# MINI_SAM_TQFP_2_54_BB_2017_01_17_004.net
KiCad netlist of a schematic drawn in EAGLE
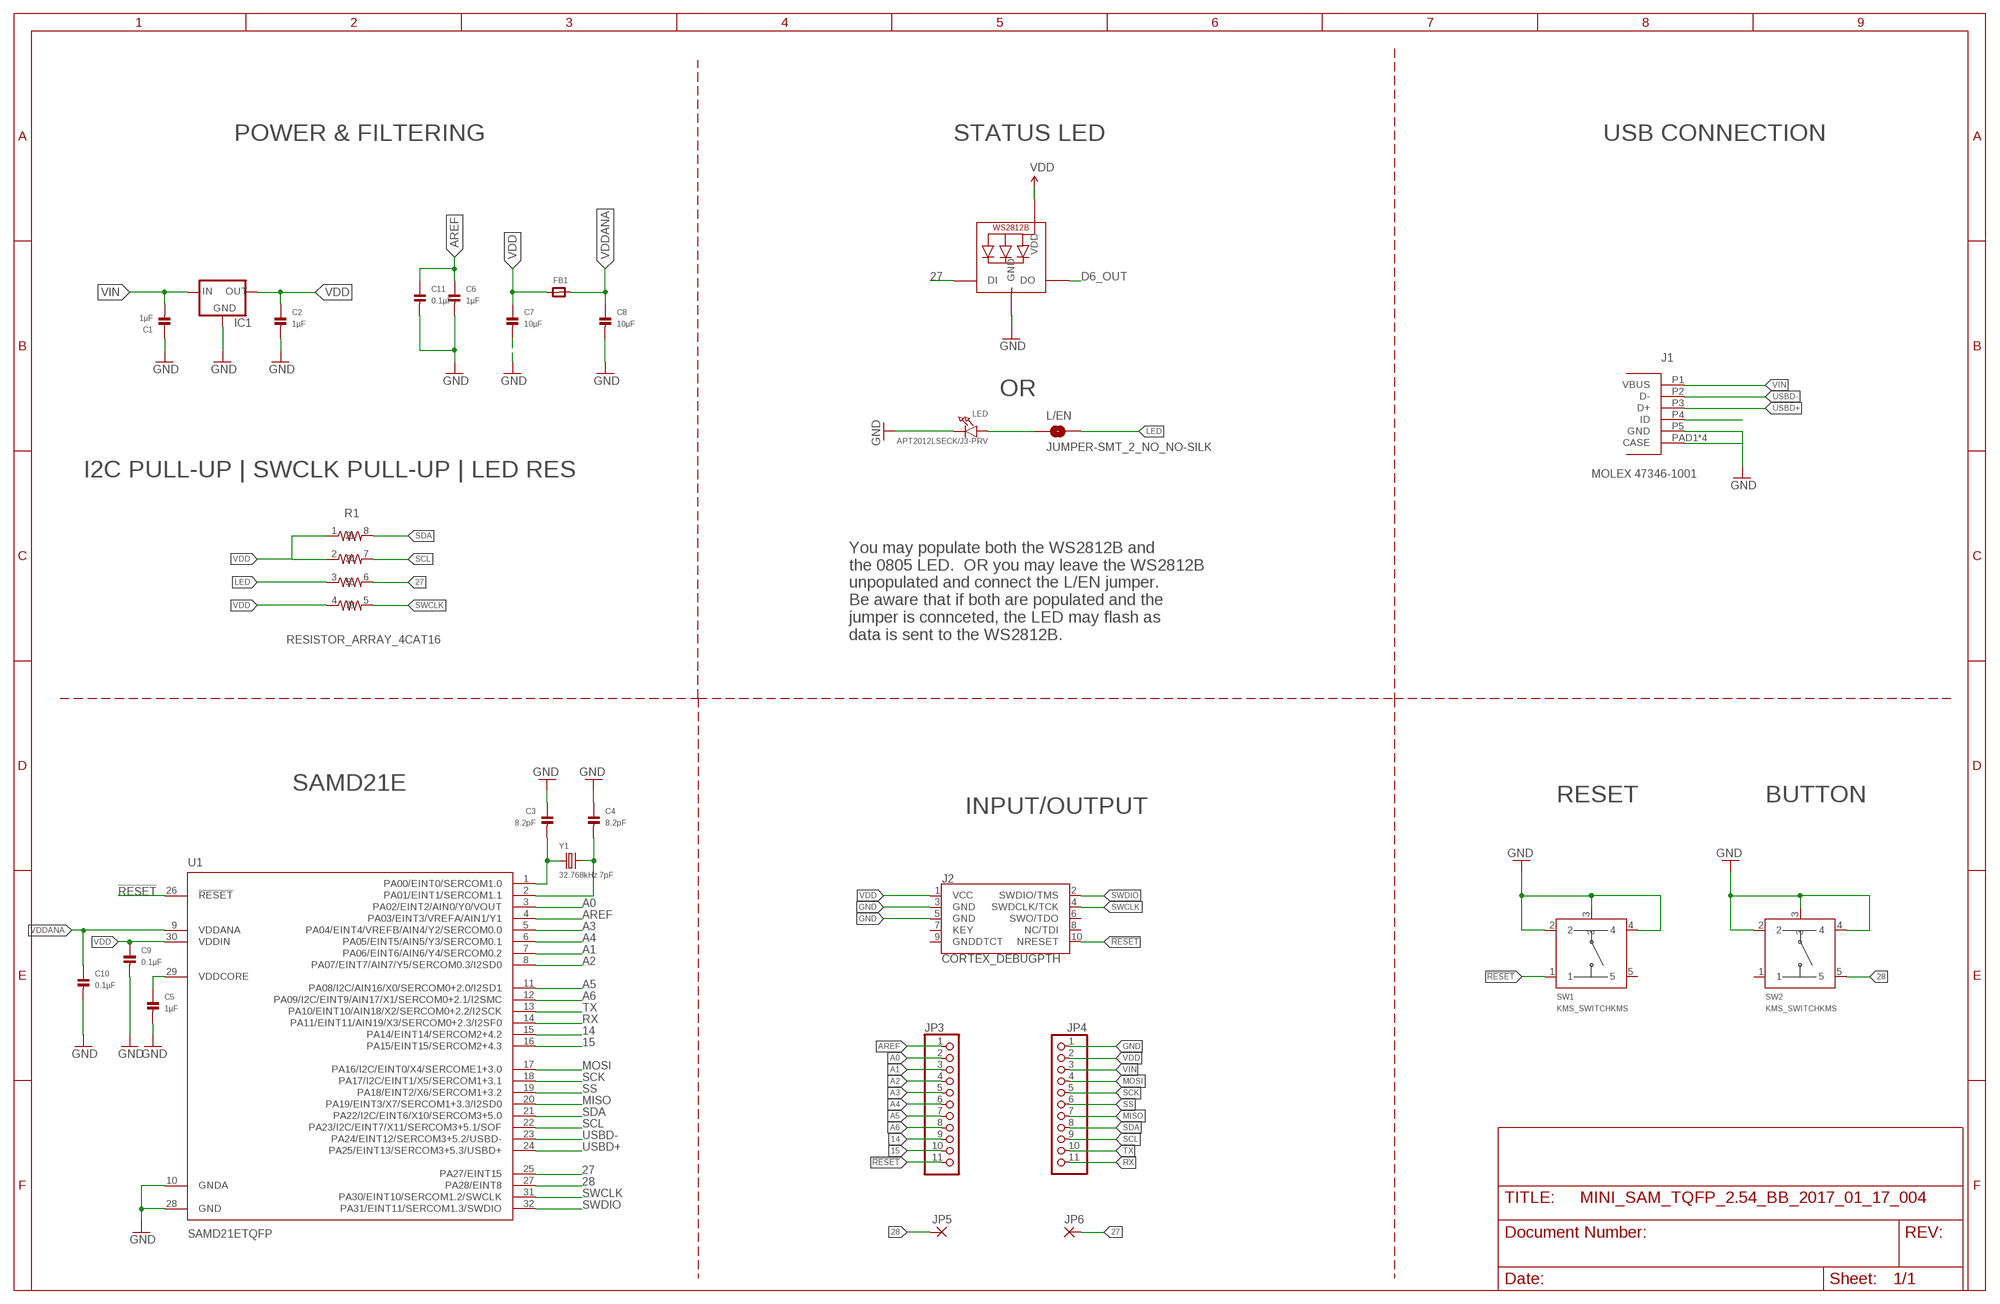
[diagram p0: schematic, sheet 1]

(export (version "E")
  (design (tool "Eeschema 10.0.6"))
  (components
    (comp (ref "C1")
      (value "1µF")
      (footprint "eagle-import:_0805MP")
      (libsource (lib "eagle-import") (part "CAP_CERAMIC_0805MP"))
    )
    (comp (ref "C2")
      (value "1µF")
      (footprint "eagle-import:_0805MP")
      (libsource (lib "eagle-import") (part "CAP_CERAMIC_0805MP"))
    )
    (comp (ref "C3")
      (value "8.2pF")
      (footprint "eagle-import:_0805MP")
      (libsource (lib "eagle-import") (part "CAP_CERAMIC_0805MP"))
    )
    (comp (ref "C4")
      (value "8.2pF")
      (footprint "eagle-import:_0805MP")
      (libsource (lib "eagle-import") (part "CAP_CERAMIC_0805MP"))
    )
    (comp (ref "C5")
      (value "1µF")
      (footprint "eagle-import:_0805MP")
      (libsource (lib "eagle-import") (part "CAP_CERAMIC_0805MP"))
    )
    (comp (ref "C6")
      (value "1µF")
      (footprint "eagle-import:_0805MP")
      (libsource (lib "eagle-import") (part "CAP_CERAMIC_0805MP"))
    )
    (comp (ref "C7")
      (value "10µF")
      (footprint "eagle-import:_0805MP")
      (libsource (lib "eagle-import") (part "CAP_CERAMIC_0805MP"))
    )
    (comp (ref "C8")
      (value "10µF")
      (footprint "eagle-import:_0805MP")
      (libsource (lib "eagle-import") (part "CAP_CERAMIC_0805MP"))
    )
    (comp (ref "C9")
      (value "0.1µF")
      (footprint "eagle-import:_0805MP")
      (libsource (lib "eagle-import") (part "CAP_CERAMIC_0805MP"))
    )
    (comp (ref "C10")
      (value "0.1µF")
      (footprint "eagle-import:_0805MP")
      (libsource (lib "eagle-import") (part "CAP_CERAMIC_0805MP"))
    )
    (comp (ref "C11")
      (value "0.1µF")
      (footprint "eagle-import:_0805MP")
      (libsource (lib "eagle-import") (part "CAP_CERAMIC_0805MP"))
    )
    (comp (ref "FB1")
      (value "FERRITE_0805MP")
      (footprint "eagle-import:_0805MP")
      (libsource (lib "eagle-import") (part "FERRITE_0805MP"))
    )
    (comp (ref "IC1")
      (value "MCP1700")
      (footprint "eagle-import:SOT23")
      (libsource (lib "eagle-import") (part "MCP1700"))
    )
    (comp (ref "J1")
      (value "MOLEX_47346-100147346")
      (footprint "eagle-import:MOLEX_47346-1001")
      (libsource (lib "eagle-import") (part "MOLEX_47346-100147346"))
    )
    (comp (ref "J2")
      (value "CORTEX_DEBUGPTH")
      (footprint "eagle-import:2X5-PTH-1.27MM")
      (libsource (lib "eagle-import") (part "CORTEX_DEBUGPTH"))
    )
    (comp (ref "JP3")
      (value "PINHD-1X111X11_SMT")
      (footprint "eagle-import:1X11_SMT")
      (libsource (lib "eagle-import") (part "PINHD-1X111X11_SMT"))
    )
    (comp (ref "JP4")
      (value "PINHD-1X111X11_SMT")
      (footprint "eagle-import:1X11_SMT")
      (libsource (lib "eagle-import") (part "PINHD-1X111X11_SMT"))
    )
    (comp (ref "JP5")
      (value "FR11_PAD2.5MMX1.5MM")
      (footprint "eagle-import:SMD2.5MMX1.5MM")
      (libsource (lib "eagle-import") (part "FR11_PAD2.5MMX1.5MM"))
    )
    (comp (ref "JP6")
      (value "FR11_PAD2.5MMX1.5MM")
      (footprint "eagle-import:SMD2.5MMX1.5MM")
      (libsource (lib "eagle-import") (part "FR11_PAD2.5MMX1.5MM"))
    )
    (comp (ref "L/EN")
      (value "JUMPER-SMT_2_NO_NO-SILK")
      (footprint "eagle-import:SMT-JUMPER_2_NO_NO-SILK")
      (libsource (lib "eagle-import") (part "JUMPER-SMT_2_NO_NO-SILK"))
    )
    (comp (ref "LED")
      (value "APT2012LSECK/J3-PRV")
      (footprint "eagle-import:CHIPLED_0805_NOOUTLINE")
      (libsource (lib "eagle-import") (part "LED0805_NOOUTLINE"))
    )
    (comp (ref "R1")
      (value "RESISTOR_ARRAY_4CAT16")
      (footprint "eagle-import:CAT16_ARRAY")
      (libsource (lib "eagle-import") (part "RESISTOR_ARRAY_4CAT16"))
    )
    (comp (ref "STATUS")
      (value "WS2812B3535")
      (footprint "eagle-import:LED3535")
      (libsource (lib "eagle-import") (part "WS2812B3535"))
    )
    (comp (ref "SW1")
      (value "KMS_SWITCHKMS")
      (footprint "eagle-import:KMS_SWITCH")
      (libsource (lib "eagle-import") (part "KMS_SWITCHKMS"))
    )
    (comp (ref "SW2")
      (value "KMS_SWITCHKMS")
      (footprint "eagle-import:KMS_SWITCH")
      (libsource (lib "eagle-import") (part "KMS_SWITCHKMS"))
    )
    (comp (ref "U1")
      (value "SAMD21ETQFP")
      (footprint "eagle-import:TQFP32-08")
      (libsource (lib "eagle-import") (part "SAMD21ETQFP"))
    )
    (comp (ref "Y1")
      (value "32.768kHz 7pF")
      (footprint "eagle-import:_0805MP")
      (libsource (lib "eagle-import") (part "CRYSTAL0805PACKAGE"))
    )
  )
  (nets
    (net (code "1") (name "/D6_OUT") (class "Default")
      (node (ref "STATUS") (pin "3") (pinfunction "DO_3") (pintype "output"))
    )
    (net (code "2") (name "/~{RESET}") (class "Default")
      (node (ref "J2") (pin "10") (pinfunction "NRESET_10") (pintype "bidirectional"))
      (node (ref "JP3") (pin "11") (pinfunction "11_11") (pintype "passive"))
      (node (ref "SW1") (pin "1") (pinfunction "1_1") (pintype "bidirectional"))
      (node (ref "U1") (pin "26") (pinfunction "~{RESET}_26") (pintype "bidirectional"))
    )
    (net (code "3") (name "14") (class "Default")
      (node (ref "JP3") (pin "9") (pinfunction "9_9") (pintype "passive"))
      (node (ref "U1") (pin "15") (pinfunction "PA14/EINT14/SERCOM2+4.2_15") (pintype "bidirectional"))
    )
    (net (code "4") (name "15") (class "Default")
      (node (ref "JP3") (pin "10") (pinfunction "10_10") (pintype "passive"))
      (node (ref "U1") (pin "16") (pinfunction "PA15/EINT15/SERCOM2+4.3_16") (pintype "bidirectional"))
    )
    (net (code "5") (name "27") (class "Default")
      (node (ref "JP6") (pin "P$1") (pinfunction "P_P$1") (pintype "passive"))
      (node (ref "R1") (pin "6") (pinfunction "5_6") (pintype "passive"))
      (node (ref "STATUS") (pin "1") (pinfunction "DI_1") (pintype "input"))
      (node (ref "U1") (pin "25") (pinfunction "PA27/EINT15_25") (pintype "bidirectional"))
    )
    (net (code "6") (name "28") (class "Default")
      (node (ref "JP5") (pin "P$1") (pinfunction "P_P$1") (pintype "passive"))
      (node (ref "SW2") (pin "5") (pinfunction "5_5") (pintype "bidirectional"))
      (node (ref "U1") (pin "27") (pinfunction "PA28/EINT8_27") (pintype "bidirectional"))
    )
    (net (code "7") (name "A0") (class "Default")
      (node (ref "JP3") (pin "2") (pinfunction "2_2") (pintype "passive"))
      (node (ref "U1") (pin "3") (pinfunction "PA02/EINT2/AIN0/Y0/VOUT_3") (pintype "bidirectional"))
    )
    (net (code "8") (name "A1") (class "Default")
      (node (ref "JP3") (pin "3") (pinfunction "3_3") (pintype "passive"))
      (node (ref "U1") (pin "7") (pinfunction "PA06/EINT6/AIN6/Y4/SERCOM0.2_7") (pintype "bidirectional"))
    )
    (net (code "9") (name "A2") (class "Default")
      (node (ref "JP3") (pin "4") (pinfunction "4_4") (pintype "passive"))
      (node (ref "U1") (pin "8") (pinfunction "PA07/EINT7/AIN7/Y5/SERCOM0.3/I2SD0_8") (pintype "bidirectional"))
    )
    (net (code "10") (name "A3") (class "Default")
      (node (ref "JP3") (pin "5") (pinfunction "5_5") (pintype "passive"))
      (node (ref "U1") (pin "5") (pinfunction "PA04/EINT4/VREFB/AIN4/Y2/SERCOM0.0_5") (pintype "bidirectional"))
    )
    (net (code "11") (name "A4") (class "Default")
      (node (ref "JP3") (pin "6") (pinfunction "6_6") (pintype "passive"))
      (node (ref "U1") (pin "6") (pinfunction "PA05/EINT5/AIN5/Y3/SERCOM0.1_6") (pintype "bidirectional"))
    )
    (net (code "12") (name "A5") (class "Default")
      (node (ref "JP3") (pin "7") (pinfunction "7_7") (pintype "passive"))
      (node (ref "U1") (pin "11") (pinfunction "PA08/I2C/AIN16/X0/SERCOM0+2.0/I2SD1_11") (pintype "bidirectional"))
    )
    (net (code "13") (name "A6") (class "Default")
      (node (ref "JP3") (pin "8") (pinfunction "8_8") (pintype "passive"))
      (node (ref "U1") (pin "12") (pinfunction "PA09/I2C/EINT9/AIN17/X1/SERCOM0+2.1/I2SMC_12") (pintype "bidirectional"))
    )
    (net (code "14") (name "AREF") (class "Default")
      (node (ref "C11") (pin "1") (pinfunction "P$1_1") (pintype "passive"))
      (node (ref "C6") (pin "1") (pinfunction "P$1_1") (pintype "passive"))
      (node (ref "JP3") (pin "1") (pinfunction "1_1") (pintype "passive"))
      (node (ref "U1") (pin "4") (pinfunction "PA03/EINT3/VREFA/AIN1/Y1_4") (pintype "bidirectional"))
    )
    (net (code "15") (name "GND") (class "Default")
      (node (ref "C1") (pin "1") (pinfunction "P$1_1") (pintype "passive"))
      (node (ref "C10") (pin "2") (pinfunction "P$2_2") (pintype "passive"))
      (node (ref "C11") (pin "2") (pinfunction "P$2_2") (pintype "passive"))
      (node (ref "C2") (pin "2") (pinfunction "P$2_2") (pintype "passive"))
      (node (ref "C3") (pin "1") (pinfunction "P$1_1") (pintype "passive"))
      (node (ref "C4") (pin "1") (pinfunction "P$1_1") (pintype "passive"))
      (node (ref "C5") (pin "2") (pinfunction "P$2_2") (pintype "passive"))
      (node (ref "C6") (pin "2") (pinfunction "P$2_2") (pintype "passive"))
      (node (ref "C7") (pin "2") (pinfunction "P$2_2") (pintype "passive"))
      (node (ref "C8") (pin "2") (pinfunction "P$2_2") (pintype "passive"))
      (node (ref "C9") (pin "2") (pinfunction "P$2_2") (pintype "passive"))
      (node (ref "IC1") (pin "1") (pinfunction "GND_1") (pintype "input"))
      (node (ref "J1") (pin "P5") (pinfunction "GND_P5") (pintype "power_in"))
      (node (ref "J1") (pin "PAD1") (pinfunction "CASE_PAD1") (pintype "bidirectional"))
      (node (ref "J1") (pin "PAD2") (pinfunction "CASE_PAD2") (pintype "bidirectional"))
      (node (ref "J1") (pin "PAD3") (pinfunction "CASE_PAD3") (pintype "bidirectional"))
      (node (ref "J1") (pin "PAD4") (pinfunction "CASE_PAD4") (pintype "bidirectional"))
      (node (ref "J2") (pin "3") (pinfunction "GND_3") (pintype "bidirectional"))
      (node (ref "J2") (pin "5") (pinfunction "GND_5") (pintype "bidirectional"))
      (node (ref "JP4") (pin "1") (pinfunction "1_1") (pintype "passive"))
      (node (ref "LED") (pin "C") (pinfunction "C_C") (pintype "passive"))
      (node (ref "STATUS") (pin "4") (pinfunction "GND_4") (pintype "power_in"))
      (node (ref "SW1") (pin "2") (pinfunction "2_2") (pintype "bidirectional"))
      (node (ref "SW1") (pin "3") (pinfunction "3_3") (pintype "bidirectional"))
      (node (ref "SW1") (pin "4") (pinfunction "4_4") (pintype "bidirectional"))
      (node (ref "SW2") (pin "2") (pinfunction "2_2") (pintype "bidirectional"))
      (node (ref "SW2") (pin "3") (pinfunction "3_3") (pintype "bidirectional"))
      (node (ref "SW2") (pin "4") (pinfunction "4_4") (pintype "bidirectional"))
      (node (ref "U1") (pin "10") (pinfunction "GNDA_10") (pintype "power_in"))
      (node (ref "U1") (pin "28") (pinfunction "GND_28") (pintype "power_in"))
    )
    (net (code "16") (name "LED") (class "Default")
      (node (ref "L/EN") (pin "2") (pinfunction "2_2") (pintype "passive"))
      (node (ref "R1") (pin "3") (pinfunction "6_3") (pintype "passive"))
    )
    (net (code "17") (name "MISO") (class "Default")
      (node (ref "JP4") (pin "7") (pinfunction "7_7") (pintype "passive"))
      (node (ref "U1") (pin "20") (pinfunction "PA19/EINT3/X7/SERCOM1+3.3/I2SD0_20") (pintype "bidirectional"))
    )
    (net (code "18") (name "MOSI") (class "Default")
      (node (ref "JP4") (pin "4") (pinfunction "4_4") (pintype "passive"))
      (node (ref "U1") (pin "17") (pinfunction "PA16/I2C/EINT0/X4/SERCOME1+3.0_17") (pintype "bidirectional"))
    )
    (net (code "19") (name "Net-(C3-P$2)") (class "Default")
      (node (ref "C3") (pin "2") (pinfunction "P$2_2") (pintype "passive"))
      (node (ref "U1") (pin "1") (pinfunction "PA00/EINT0/SERCOM1.0_1") (pintype "bidirectional"))
      (node (ref "Y1") (pin "1") (pinfunction "1_1") (pintype "passive"))
    )
    (net (code "20") (name "Net-(C4-P$2)") (class "Default")
      (node (ref "C4") (pin "2") (pinfunction "P$2_2") (pintype "passive"))
      (node (ref "U1") (pin "2") (pinfunction "PA01/EINT1/SERCOM1.1_2") (pintype "bidirectional"))
      (node (ref "Y1") (pin "2") (pinfunction "2_2") (pintype "passive"))
    )
    (net (code "21") (name "Net-(C5-P$1)") (class "Default")
      (node (ref "C5") (pin "1") (pinfunction "P$1_1") (pintype "passive"))
      (node (ref "U1") (pin "29") (pinfunction "VDDCORE_29") (pintype "power_in"))
    )
    (net (code "22") (name "Net-(L/EN-Pad1)") (class "Default")
      (node (ref "L/EN") (pin "1") (pinfunction "1_1") (pintype "passive"))
      (node (ref "LED") (pin "A") (pinfunction "A_A") (pintype "passive"))
    )
    (net (code "23") (name "RX") (class "Default")
      (node (ref "JP4") (pin "11") (pinfunction "11_11") (pintype "passive"))
      (node (ref "U1") (pin "14") (pinfunction "PA11/EINT11/AIN19/X3/SERCOM0+2.3/I2SF0_14") (pintype "bidirectional"))
    )
    (net (code "24") (name "SCK") (class "Default")
      (node (ref "JP4") (pin "5") (pinfunction "5_5") (pintype "passive"))
      (node (ref "U1") (pin "18") (pinfunction "PA17/I2C/EINT1/X5/SERCOM1+3.1_18") (pintype "bidirectional"))
    )
    (net (code "25") (name "SCL") (class "Default")
      (node (ref "JP4") (pin "9") (pinfunction "9_9") (pintype "passive"))
      (node (ref "R1") (pin "7") (pinfunction "3_7") (pintype "passive"))
      (node (ref "U1") (pin "22") (pinfunction "PA23/I2C/EINT7/X11/SERCOM3+5.1/SOF_22") (pintype "bidirectional"))
    )
    (net (code "26") (name "SDA") (class "Default")
      (node (ref "JP4") (pin "8") (pinfunction "8_8") (pintype "passive"))
      (node (ref "R1") (pin "8") (pinfunction "2_8") (pintype "passive"))
      (node (ref "U1") (pin "21") (pinfunction "PA22/I2C/EINT6/X10/SERCOM3+5.0_21") (pintype "bidirectional"))
    )
    (net (code "27") (name "SS") (class "Default")
      (node (ref "JP4") (pin "6") (pinfunction "6_6") (pintype "passive"))
      (node (ref "U1") (pin "19") (pinfunction "PA18/EINT2/X6/SERCOM1+3.2_19") (pintype "bidirectional"))
    )
    (net (code "28") (name "SWCLK") (class "Default")
      (node (ref "J2") (pin "4") (pinfunction "SWDCLK/TCK_4") (pintype "bidirectional"))
      (node (ref "R1") (pin "5") (pinfunction "7_5") (pintype "passive"))
      (node (ref "U1") (pin "31") (pinfunction "PA30/EINT10/SERCOM1.2/SWCLK_31") (pintype "bidirectional"))
    )
    (net (code "29") (name "SWDIO") (class "Default")
      (node (ref "J2") (pin "2") (pinfunction "SWDIO/TMS_2") (pintype "bidirectional"))
      (node (ref "U1") (pin "32") (pinfunction "PA31/EINT11/SERCOM1.3/SWDIO_32") (pintype "bidirectional"))
    )
    (net (code "30") (name "TX") (class "Default")
      (node (ref "JP4") (pin "10") (pinfunction "10_10") (pintype "passive"))
      (node (ref "U1") (pin "13") (pinfunction "PA10/EINT10/AIN18/X2/SERCOM0+2.2/I2SCK_13") (pintype "bidirectional"))
    )
    (net (code "31") (name "USBD+") (class "Default")
      (node (ref "J1") (pin "P3") (pinfunction "D+_P3") (pintype "bidirectional"))
      (node (ref "U1") (pin "24") (pinfunction "PA25/EINT13/SERCOM3+5.3/USBD+_24") (pintype "bidirectional"))
    )
    (net (code "32") (name "USBD-") (class "Default")
      (node (ref "J1") (pin "P2") (pinfunction "D-_P2") (pintype "bidirectional"))
      (node (ref "U1") (pin "23") (pinfunction "PA24/EINT12/SERCOM3+5.2/USBD-_23") (pintype "bidirectional"))
    )
    (net (code "33") (name "VDD") (class "Default")
      (node (ref "C2") (pin "1") (pinfunction "P$1_1") (pintype "passive"))
      (node (ref "C7") (pin "1") (pinfunction "P$1_1") (pintype "passive"))
      (node (ref "C9") (pin "1") (pinfunction "P$1_1") (pintype "passive"))
      (node (ref "FB1") (pin "1") (pinfunction "P$1_1") (pintype "passive"))
      (node (ref "IC1") (pin "2") (pinfunction "OUT_2") (pintype "passive"))
      (node (ref "J2") (pin "1") (pinfunction "VCC_1") (pintype "bidirectional"))
      (node (ref "JP4") (pin "2") (pinfunction "2_2") (pintype "passive"))
      (node (ref "R1") (pin "1") (pinfunction "1_1") (pintype "passive"))
      (node (ref "R1") (pin "2") (pinfunction "4_2") (pintype "passive"))
      (node (ref "R1") (pin "4") (pinfunction "8_4") (pintype "passive"))
      (node (ref "STATUS") (pin "2") (pinfunction "VDD_2") (pintype "power_in"))
      (node (ref "U1") (pin "30") (pinfunction "VDDIN_30") (pintype "power_in"))
    )
    (net (code "34") (name "VDDANA") (class "Default")
      (node (ref "C10") (pin "1") (pinfunction "P$1_1") (pintype "passive"))
      (node (ref "C8") (pin "1") (pinfunction "P$1_1") (pintype "passive"))
      (node (ref "FB1") (pin "2") (pinfunction "P$2_2") (pintype "passive"))
      (node (ref "U1") (pin "9") (pinfunction "VDDANA_9") (pintype "power_in"))
    )
    (net (code "35") (name "VIN") (class "Default")
      (node (ref "C1") (pin "2") (pinfunction "P$2_2") (pintype "passive"))
      (node (ref "IC1") (pin "3") (pinfunction "IN_3") (pintype "input"))
      (node (ref "J1") (pin "P1") (pinfunction "VBUS_P1") (pintype "power_in"))
      (node (ref "JP4") (pin "3") (pinfunction "3_3") (pintype "passive"))
    )
    (net (code "36") (name "unconnected-(J1-ID-PadP4)") (class "Default")
      (node (ref "J1") (pin "P4") (pinfunction "ID_P4") (pintype "bidirectional"))
    )
    (net (code "37") (name "unconnected-(J2-GNDDTCT-Pad9)") (class "Default")
      (node (ref "J2") (pin "9") (pinfunction "GNDDTCT_9") (pintype "bidirectional"))
    )
    (net (code "38") (name "unconnected-(J2-KEY-Pad7)") (class "Default")
      (node (ref "J2") (pin "7") (pinfunction "KEY_7") (pintype "bidirectional"))
    )
    (net (code "39") (name "unconnected-(J2-NC{slash}TDI-Pad8)") (class "Default")
      (node (ref "J2") (pin "8") (pinfunction "NC/TDI_8") (pintype "bidirectional"))
    )
    (net (code "40") (name "unconnected-(J2-SWO{slash}TDO-Pad6)") (class "Default")
      (node (ref "J2") (pin "6") (pinfunction "SWO/TDO_6") (pintype "bidirectional"))
    )
    (net (code "41") (name "unconnected-(SW1-Pad5)") (class "Default")
      (node (ref "SW1") (pin "5") (pinfunction "5_5") (pintype "bidirectional"))
    )
    (net (code "42") (name "unconnected-(SW2-Pad1)") (class "Default")
      (node (ref "SW2") (pin "1") (pinfunction "1_1") (pintype "bidirectional"))
    )
  )
)
